# ControlBoard.net
KiCad netlist of a schematic drawn in Altium Designer
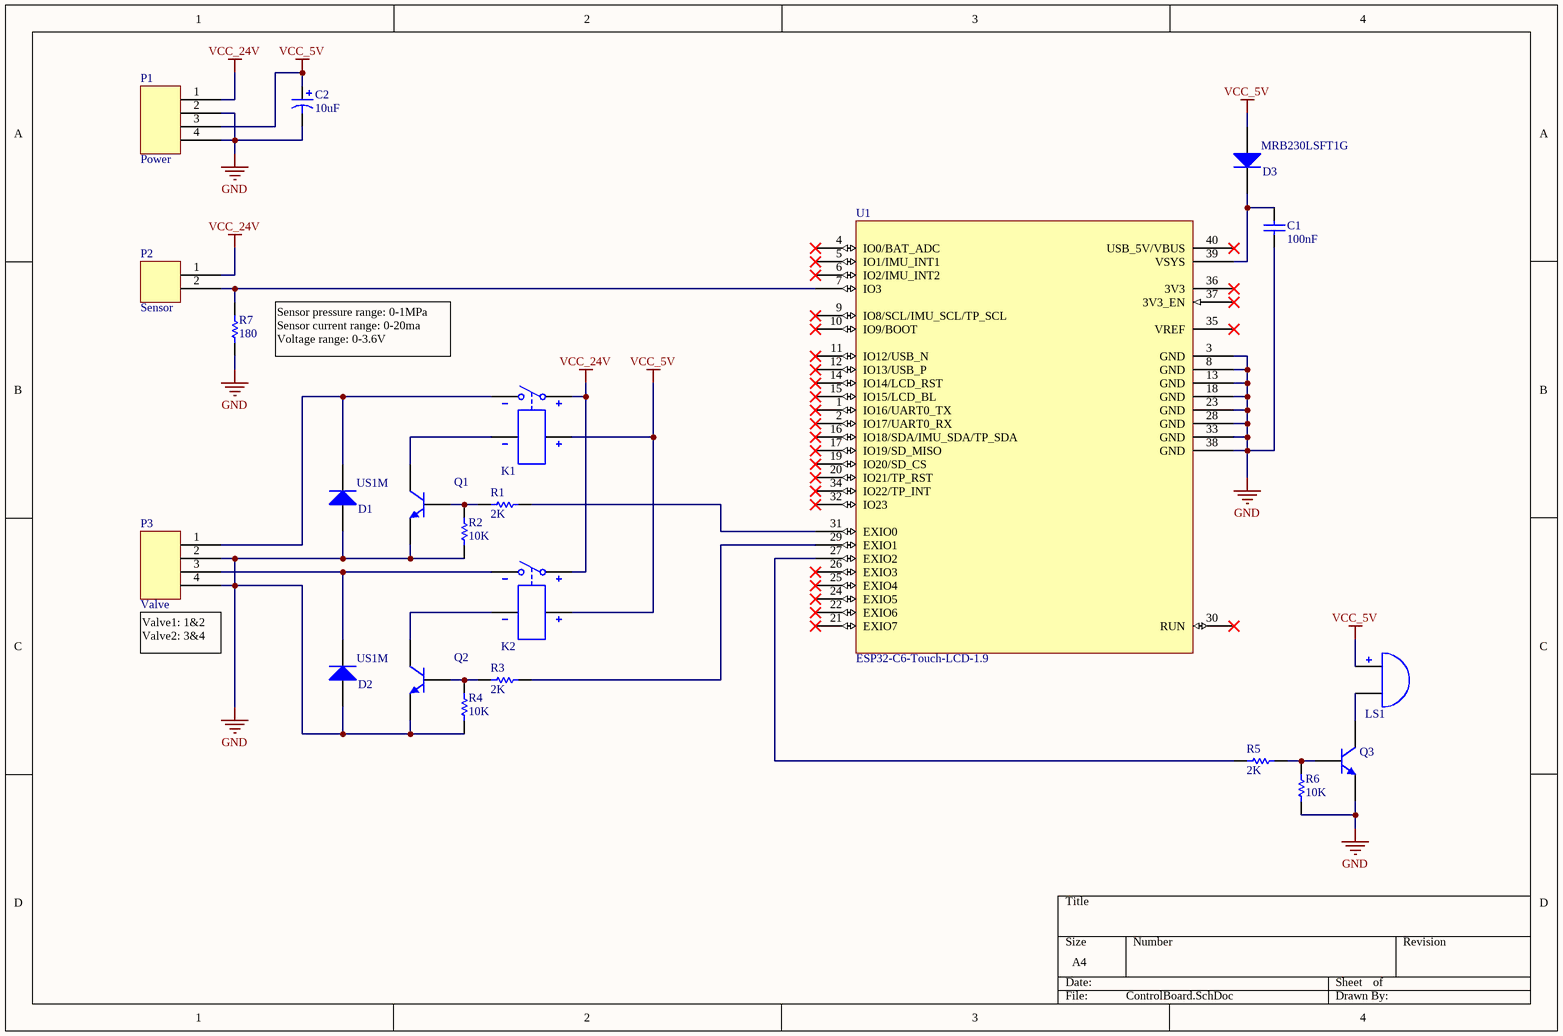
[diagram p0: ControlBoard.SchDoc]

(export (version "E")
  (design (tool "Eeschema 10.0.6"))
  (components
    (comp (ref "C1")
      (value "100nF")
      (footprint "CAP0603/M")
      (description "Capacitor")
      (fields (field (name "Comment") "Cap") (field (name "PUBLISHER") "Altium Limited"))
      (libsource (lib "BoilerAutoFill") (part "Cap"))
    )
    (comp (ref "C2")
      (value "10uF")
      (footprint "CAPMP6032/M")
      (description "Polarized Capacitor")
      (fields (field (name "Comment") "Cap Pol") (field (name "PUBLISHER") "Altium Limited"))
      (libsource (lib "BoilerAutoFill") (part "CapPol"))
    )
    (comp (ref "D1")
      (value "US1M")
      (footprint "DO-214AC/M")
      (description "1 Amp Ultra Fast Rectifier SMA")
      (libsource (lib "BoilerAutoFill") (part "Diode US1M"))
    )
    (comp (ref "D2")
      (value "US1M")
      (footprint "DO-214AC/M")
      (description "1 Amp Ultra Fast Rectifier SMA")
      (libsource (lib "BoilerAutoFill") (part "Diode US1M"))
    )
    (comp (ref "D3")
      (value "MRB230LSFT1G")
      (footprint "SOD-123FL/M")
      (description "Schottky Barrier Rectifier 2A 30V")
      (libsource (lib "BoilerAutoFill") (part "Diode MRB230LSFT1G"))
    )
    (comp (ref "K1")
      (value "ENMG Solid State Relay")
      (footprint "PMN5D6132")
      (description "ENMG Solid State Relay PMN5D6132")
      (libsource (lib "BoilerAutoFill") (part "PMN5D6132"))
    )
    (comp (ref "K2")
      (value "ENMG Solid State Relay")
      (footprint "PMN5D6132")
      (description "ENMG Solid State Relay PMN5D6132")
      (libsource (lib "BoilerAutoFill") (part "PMN5D6132"))
    )
    (comp (ref "LS1")
      (value "Buzzer")
      (footprint "Buzzer-2310")
      (libsource (lib "BoilerAutoFill") (part "Buzzer"))
    )
    (comp (ref "P1")
      (value "Power")
      (footprint "KEFA/KF128L-3.81-04P")
      (libsource (lib "BoilerAutoFill") (part "Header-4"))
    )
    (comp (ref "P2")
      (value "Sensor")
      (footprint "KEFA/KF128L-3.81-02P")
      (libsource (lib "BoilerAutoFill") (part "Header-2"))
    )
    (comp (ref "P3")
      (value "Valve")
      (footprint "KEFA/KF128L-3.81-04P")
      (libsource (lib "BoilerAutoFill") (part "Header-4"))
    )
    (comp (ref "Q1")
      (value "NPN")
      (footprint "SOT-23/M")
      (description "NPN Bipolar Transistor")
      (libsource (lib "BoilerAutoFill") (part "MMBT5551"))
    )
    (comp (ref "Q2")
      (value "NPN")
      (footprint "SOT-23/M")
      (description "NPN Bipolar Transistor")
      (libsource (lib "BoilerAutoFill") (part "MMBT5551"))
    )
    (comp (ref "Q3")
      (value "NPN")
      (footprint "SOT-23/M")
      (description "NPN Bipolar Transistor")
      (libsource (lib "BoilerAutoFill") (part "MMBT5551"))
    )
    (comp (ref "R1")
      (value "2K")
      (footprint "RES0603/M")
      (description "Resistor")
      (fields (field (name "Comment") "Res") (field (name "PUBLISHER") "Altium Limited"))
      (libsource (lib "BoilerAutoFill") (part "Res"))
    )
    (comp (ref "R2")
      (value "10K")
      (footprint "RES0603/M")
      (description "Resistor")
      (fields (field (name "Comment") "Res") (field (name "PUBLISHER") "Altium Limited"))
      (libsource (lib "BoilerAutoFill") (part "Res"))
    )
    (comp (ref "R3")
      (value "2K")
      (footprint "RES0603/M")
      (description "Resistor")
      (fields (field (name "Comment") "Res") (field (name "PUBLISHER") "Altium Limited"))
      (libsource (lib "BoilerAutoFill") (part "Res"))
    )
    (comp (ref "R4")
      (value "10K")
      (footprint "RES0603/M")
      (description "Resistor")
      (fields (field (name "Comment") "Res") (field (name "PUBLISHER") "Altium Limited"))
      (libsource (lib "BoilerAutoFill") (part "Res"))
    )
    (comp (ref "R5")
      (value "2K")
      (footprint "RES0603/M")
      (description "Resistor")
      (fields (field (name "Comment") "Res") (field (name "PUBLISHER") "Altium Limited"))
      (libsource (lib "BoilerAutoFill") (part "Res"))
    )
    (comp (ref "R6")
      (value "10K")
      (footprint "RES0603/M")
      (description "Resistor")
      (fields (field (name "Comment") "Res") (field (name "PUBLISHER") "Altium Limited"))
      (libsource (lib "BoilerAutoFill") (part "Res"))
    )
    (comp (ref "R7")
      (value "180")
      (footprint "RES2512/L")
      (description "Resistor")
      (fields (field (name "Comment") "Res") (field (name "PUBLISHER") "Altium Limited"))
      (libsource (lib "BoilerAutoFill") (part "Res"))
    )
    (comp (ref "U1")
      (value "ESP32-C6-Touch-LCD-1.9")
      (footprint "ESP32-C6-Touch-LCD-1.9_Socket")
      (description "WaveShare ESP32-C6-Touch-LCD-1.9")
      (libsource (lib "BoilerAutoFill") (part "ESP32-C6-Touch-LCD-1.9"))
    )
  )
  (nets
    (net (code "1") (name "GND") (class "Default")
      (node (ref "C1") (pin "2") (pinfunction "2_2") (pintype "passive"))
      (node (ref "C2") (pin "N") (pinfunction "N_N") (pintype "passive"))
      (node (ref "D1") (pin "P") (pinfunction "A_P") (pintype "passive"))
      (node (ref "D2") (pin "P") (pinfunction "A_P") (pintype "passive"))
      (node (ref "P1") (pin "2") (pintype "passive"))
      (node (ref "P1") (pin "4") (pintype "passive"))
      (node (ref "P3") (pin "2") (pintype "passive"))
      (node (ref "P3") (pin "4") (pintype "passive"))
      (node (ref "Q1") (pin "E") (pinfunction "E_E") (pintype "passive"))
      (node (ref "Q2") (pin "E") (pinfunction "E_E") (pintype "passive"))
      (node (ref "Q3") (pin "E") (pinfunction "E_E") (pintype "passive"))
      (node (ref "R2") (pin "1") (pinfunction "1_1") (pintype "passive"))
      (node (ref "R4") (pin "1") (pinfunction "1_1") (pintype "passive"))
      (node (ref "R6") (pin "1") (pinfunction "1_1") (pintype "passive"))
      (node (ref "R7") (pin "2") (pinfunction "2_2") (pintype "passive"))
      (node (ref "U1") (pin "13") (pinfunction "GND_13") (pintype "power_in"))
      (node (ref "U1") (pin "18") (pinfunction "GND_18") (pintype "power_in"))
      (node (ref "U1") (pin "23") (pinfunction "GND_23") (pintype "power_in"))
      (node (ref "U1") (pin "28") (pinfunction "GND_28") (pintype "power_in"))
      (node (ref "U1") (pin "3") (pinfunction "GND_3") (pintype "power_in"))
      (node (ref "U1") (pin "33") (pinfunction "GND_33") (pintype "power_in"))
      (node (ref "U1") (pin "38") (pinfunction "GND_38") (pintype "power_in"))
      (node (ref "U1") (pin "8") (pinfunction "GND_8") (pintype "power_in"))
    )
    (net (code "2") (name "Net-(D1-K)") (class "Default")
      (node (ref "D1") (pin "N") (pinfunction "K_N") (pintype "passive"))
      (node (ref "K1") (pin "1") (pinfunction "1_1") (pintype "passive"))
      (node (ref "P3") (pin "1") (pintype "passive"))
    )
    (net (code "3") (name "Net-(D2-K)") (class "Default")
      (node (ref "D2") (pin "N") (pinfunction "K_N") (pintype "passive"))
      (node (ref "K2") (pin "1") (pinfunction "1_1") (pintype "passive"))
      (node (ref "P3") (pin "3") (pintype "passive"))
    )
    (net (code "4") (name "Net-(D3-K)") (class "Default")
      (node (ref "C1") (pin "1") (pinfunction "1_1") (pintype "passive"))
      (node (ref "D3") (pin "N") (pinfunction "K_N") (pintype "passive"))
      (node (ref "U1") (pin "39") (pinfunction "VSYS_39") (pintype "power_in"))
    )
    (net (code "5") (name "Net-(K1-Pad4)") (class "Default")
      (node (ref "K1") (pin "4") (pinfunction "4_4") (pintype "passive"))
      (node (ref "Q1") (pin "C") (pinfunction "C_C") (pintype "passive"))
    )
    (net (code "6") (name "Net-(K2-Pad4)") (class "Default")
      (node (ref "K2") (pin "4") (pinfunction "4_4") (pintype "passive"))
      (node (ref "Q2") (pin "C") (pinfunction "C_C") (pintype "passive"))
    )
    (net (code "7") (name "Net-(LS1-PadN)") (class "Default")
      (node (ref "LS1") (pin "N") (pinfunction "N_N") (pintype "passive"))
      (node (ref "Q3") (pin "C") (pinfunction "C_C") (pintype "passive"))
    )
    (net (code "8") (name "Net-(Q1-PadB)") (class "Default")
      (node (ref "Q1") (pin "B") (pinfunction "B_B") (pintype "passive"))
      (node (ref "R1") (pin "2") (pinfunction "2_2") (pintype "passive"))
      (node (ref "R2") (pin "2") (pinfunction "2_2") (pintype "passive"))
    )
    (net (code "9") (name "Net-(Q2-PadB)") (class "Default")
      (node (ref "Q2") (pin "B") (pinfunction "B_B") (pintype "passive"))
      (node (ref "R3") (pin "2") (pinfunction "2_2") (pintype "passive"))
      (node (ref "R4") (pin "2") (pinfunction "2_2") (pintype "passive"))
    )
    (net (code "10") (name "Net-(Q3-PadB)") (class "Default")
      (node (ref "Q3") (pin "B") (pinfunction "B_B") (pintype "passive"))
      (node (ref "R5") (pin "1") (pinfunction "1_1") (pintype "passive"))
      (node (ref "R6") (pin "2") (pinfunction "2_2") (pintype "passive"))
    )
    (net (code "11") (name "Net-(U1-EXIO0)") (class "Default")
      (node (ref "R1") (pin "1") (pinfunction "1_1") (pintype "passive"))
      (node (ref "U1") (pin "31") (pinfunction "EXIO0_31") (pintype "bidirectional"))
    )
    (net (code "12") (name "Net-(U1-EXIO1)") (class "Default")
      (node (ref "R3") (pin "1") (pinfunction "1_1") (pintype "passive"))
      (node (ref "U1") (pin "29") (pinfunction "EXIO1_29") (pintype "bidirectional"))
    )
    (net (code "13") (name "Net-(U1-EXIO2)") (class "Default")
      (node (ref "R5") (pin "2") (pinfunction "2_2") (pintype "passive"))
      (node (ref "U1") (pin "27") (pinfunction "EXIO2_27") (pintype "bidirectional"))
    )
    (net (code "14") (name "Net-(U1-IO3)") (class "Default")
      (node (ref "P2") (pin "2") (pintype "passive"))
      (node (ref "R7") (pin "1") (pinfunction "1_1") (pintype "passive"))
      (node (ref "U1") (pin "7") (pinfunction "IO3_7") (pintype "bidirectional"))
    )
    (net (code "15") (name "VCC_5V") (class "Default")
      (node (ref "C2") (pin "P") (pinfunction "P_P") (pintype "passive"))
      (node (ref "D3") (pin "P") (pinfunction "A_P") (pintype "passive"))
      (node (ref "K1") (pin "3") (pinfunction "3_3") (pintype "passive"))
      (node (ref "K2") (pin "3") (pinfunction "3_3") (pintype "passive"))
      (node (ref "LS1") (pin "P") (pinfunction "P_P") (pintype "passive"))
      (node (ref "P1") (pin "3") (pintype "passive"))
    )
    (net (code "16") (name "VCC_24V") (class "Default")
      (node (ref "K1") (pin "2") (pinfunction "2_2") (pintype "passive"))
      (node (ref "K2") (pin "2") (pinfunction "2_2") (pintype "passive"))
      (node (ref "P1") (pin "1") (pintype "passive"))
      (node (ref "P2") (pin "1") (pintype "passive"))
    )
    (net (code "17") (name "unconnected-(U1-3V3-Pad36)") (class "Default")
      (node (ref "U1") (pin "36") (pinfunction "3V3_36") (pintype "power_in+no_connect"))
    )
    (net (code "18") (name "unconnected-(U1-3V3_EN-Pad37)") (class "Default")
      (node (ref "U1") (pin "37") (pinfunction "3V3_EN_37") (pintype "input+no_connect"))
    )
    (net (code "19") (name "unconnected-(U1-EXIO3-Pad26)") (class "Default")
      (node (ref "U1") (pin "26") (pinfunction "EXIO3_26") (pintype "bidirectional+no_connect"))
    )
    (net (code "20") (name "unconnected-(U1-EXIO4-Pad25)") (class "Default")
      (node (ref "U1") (pin "25") (pinfunction "EXIO4_25") (pintype "bidirectional+no_connect"))
    )
    (net (code "21") (name "unconnected-(U1-EXIO5-Pad24)") (class "Default")
      (node (ref "U1") (pin "24") (pinfunction "EXIO5_24") (pintype "bidirectional+no_connect"))
    )
    (net (code "22") (name "unconnected-(U1-EXIO6-Pad22)") (class "Default")
      (node (ref "U1") (pin "22") (pinfunction "EXIO6_22") (pintype "bidirectional+no_connect"))
    )
    (net (code "23") (name "unconnected-(U1-EXIO7-Pad21)") (class "Default")
      (node (ref "U1") (pin "21") (pinfunction "EXIO7_21") (pintype "bidirectional+no_connect"))
    )
    (net (code "24") (name "unconnected-(U1-IO0{slash}BAT_ADC-Pad4)") (class "Default")
      (node (ref "U1") (pin "4") (pinfunction "IO0/BAT_ADC_4") (pintype "bidirectional+no_connect"))
    )
    (net (code "25") (name "unconnected-(U1-IO1{slash}IMU_INT1-Pad5)") (class "Default")
      (node (ref "U1") (pin "5") (pinfunction "IO1/IMU_INT1_5") (pintype "bidirectional+no_connect"))
    )
    (net (code "26") (name "unconnected-(U1-IO2{slash}IMU_INT2-Pad6)") (class "Default")
      (node (ref "U1") (pin "6") (pinfunction "IO2/IMU_INT2_6") (pintype "bidirectional+no_connect"))
    )
    (net (code "27") (name "unconnected-(U1-IO8{slash}SCL{slash}IMU_SCL{slash}TP_SCL-Pad9)") (class "Default")
      (node (ref "U1") (pin "9") (pinfunction "IO8/SCL/IMU_SCL/TP_SCL_9") (pintype "bidirectional+no_connect"))
    )
    (net (code "28") (name "unconnected-(U1-IO9{slash}BOOT-Pad10)") (class "Default")
      (node (ref "U1") (pin "10") (pinfunction "IO9/BOOT_10") (pintype "bidirectional+no_connect"))
    )
    (net (code "29") (name "unconnected-(U1-IO12{slash}USB_N-Pad11)") (class "Default")
      (node (ref "U1") (pin "11") (pinfunction "IO12/USB_N_11") (pintype "bidirectional+no_connect"))
    )
    (net (code "30") (name "unconnected-(U1-IO13{slash}USB_P-Pad12)") (class "Default")
      (node (ref "U1") (pin "12") (pinfunction "IO13/USB_P_12") (pintype "bidirectional+no_connect"))
    )
    (net (code "31") (name "unconnected-(U1-IO14{slash}LCD_RST-Pad14)") (class "Default")
      (node (ref "U1") (pin "14") (pinfunction "IO14/LCD_RST_14") (pintype "bidirectional+no_connect"))
    )
    (net (code "32") (name "unconnected-(U1-IO15{slash}LCD_BL-Pad15)") (class "Default")
      (node (ref "U1") (pin "15") (pinfunction "IO15/LCD_BL_15") (pintype "bidirectional+no_connect"))
    )
    (net (code "33") (name "unconnected-(U1-IO16{slash}UART0_TX-Pad1)") (class "Default")
      (node (ref "U1") (pin "1") (pinfunction "IO16/UART0_TX_1") (pintype "bidirectional+no_connect"))
    )
    (net (code "34") (name "unconnected-(U1-IO17{slash}UART0_RX-Pad2)") (class "Default")
      (node (ref "U1") (pin "2") (pinfunction "IO17/UART0_RX_2") (pintype "bidirectional+no_connect"))
    )
    (net (code "35") (name "unconnected-(U1-IO18{slash}SDA{slash}IMU_SDA{slash}TP_SDA-Pad16)") (class "Default")
      (node (ref "U1") (pin "16") (pinfunction "IO18/SDA/IMU_SDA/TP_SDA_16") (pintype "bidirectional+no_connect"))
    )
    (net (code "36") (name "unconnected-(U1-IO19{slash}SD_MISO-Pad17)") (class "Default")
      (node (ref "U1") (pin "17") (pinfunction "IO19/SD_MISO_17") (pintype "bidirectional+no_connect"))
    )
    (net (code "37") (name "unconnected-(U1-IO20{slash}SD_CS-Pad19)") (class "Default")
      (node (ref "U1") (pin "19") (pinfunction "IO20/SD_CS_19") (pintype "bidirectional+no_connect"))
    )
    (net (code "38") (name "unconnected-(U1-IO21{slash}TP_RST-Pad20)") (class "Default")
      (node (ref "U1") (pin "20") (pinfunction "IO21/TP_RST_20") (pintype "bidirectional+no_connect"))
    )
    (net (code "39") (name "unconnected-(U1-IO22{slash}TP_INT-Pad34)") (class "Default")
      (node (ref "U1") (pin "34") (pinfunction "IO22/TP_INT_34") (pintype "bidirectional+no_connect"))
    )
    (net (code "40") (name "unconnected-(U1-IO23-Pad32)") (class "Default")
      (node (ref "U1") (pin "32") (pinfunction "IO23_32") (pintype "bidirectional+no_connect"))
    )
    (net (code "41") (name "unconnected-(U1-RUN-Pad30)") (class "Default")
      (node (ref "U1") (pin "30") (pinfunction "RUN_30") (pintype "bidirectional+no_connect"))
    )
    (net (code "42") (name "unconnected-(U1-USB_5V{slash}VBUS-Pad40)") (class "Default")
      (node (ref "U1") (pin "40") (pinfunction "USB_5V/VBUS_40") (pintype "power_in+no_connect"))
    )
    (net (code "43") (name "unconnected-(U1-VREF-Pad35)") (class "Default")
      (node (ref "U1") (pin "35") (pinfunction "VREF_35") (pintype "power_in+no_connect"))
    )
  )
)
